# exam.net
KiCad netlist of a schematic drawn in Altium Designer
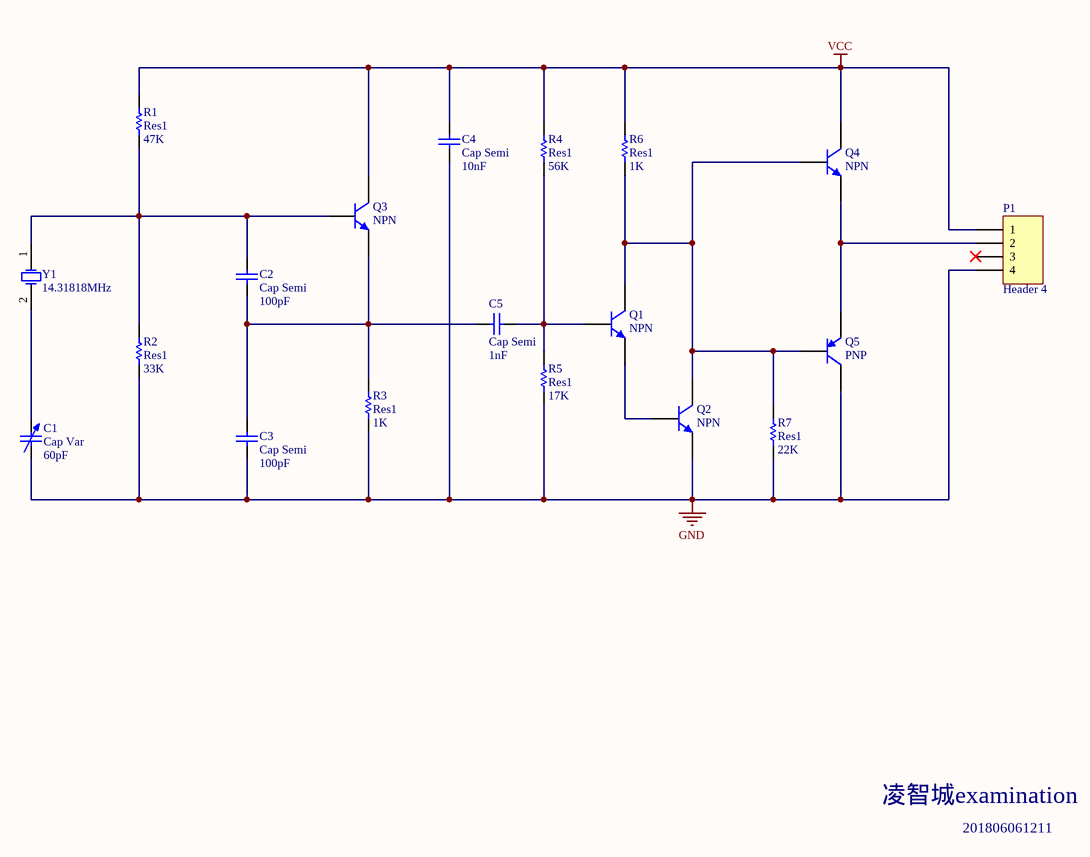
[diagram p0: exam.SchDoc]

(export (version "E")
  (design (tool "Eeschema 10.0.6"))
  (components
    (comp (ref "C1")
      (value "Cap Var")
      (footprint "C1210_N")
      (description "Variable or Adjustable Capacitor")
      (fields (field (name "ALTIUM_VALUE") "60pF") (field (name "PUBLISHER") "Altium Limited"))
      (libsource (lib "exam") (part "Cap Var"))
    )
    (comp (ref "C2")
      (value "Cap Semi")
      (footprint "C1206")
      (description "Capacitor (Semiconductor SIM Model)")
      (fields (field (name "ALTIUM_VALUE") "100pF") (field (name "PUBLISHER") "Altium Limited"))
      (libsource (lib "exam") (part "Cap Semi"))
    )
    (comp (ref "C3")
      (value "Cap Semi")
      (footprint "C1206")
      (description "Capacitor (Semiconductor SIM Model)")
      (fields (field (name "ALTIUM_VALUE") "100pF") (field (name "PUBLISHER") "Altium Limited"))
      (libsource (lib "exam") (part "Cap Semi"))
    )
    (comp (ref "C4")
      (value "Cap Semi")
      (footprint "C1206")
      (description "Capacitor (Semiconductor SIM Model)")
      (fields (field (name "ALTIUM_VALUE") "10nF") (field (name "PUBLISHER") "Altium Limited"))
      (libsource (lib "exam") (part "Cap Semi"))
    )
    (comp (ref "C5")
      (value "Cap Semi")
      (footprint "C1206")
      (description "Capacitor (Semiconductor SIM Model)")
      (fields (field (name "ALTIUM_VALUE") "1nF") (field (name "PUBLISHER") "Altium Limited"))
      (libsource (lib "exam") (part "Cap Semi"))
    )
    (comp (ref "P1")
      (value "Header 4")
      (footprint "HDR1X4")
      (description "Header, 4-Pin")
      (fields (field (name "PUBLISHER") "Altium Limited"))
      (libsource (lib "exam") (part "Header 4"))
    )
    (comp (ref "Q1")
      (value "NPN")
      (footprint "TO-226-AA")
      (description "NPN Bipolar Transistor")
      (fields (field (name "PUBLISHER") "Altium Limited"))
      (libsource (lib "exam") (part "NPN"))
    )
    (comp (ref "Q2")
      (value "NPN")
      (footprint "TO-226-AA")
      (description "NPN Bipolar Transistor")
      (fields (field (name "PUBLISHER") "Altium Limited"))
      (libsource (lib "exam") (part "NPN"))
    )
    (comp (ref "Q3")
      (value "NPN")
      (footprint "TO-226-AA")
      (description "NPN Bipolar Transistor")
      (fields (field (name "PUBLISHER") "Altium Limited"))
      (libsource (lib "exam") (part "NPN"))
    )
    (comp (ref "Q4")
      (value "NPN")
      (footprint "TO-226-AA")
      (description "NPN Bipolar Transistor")
      (fields (field (name "PUBLISHER") "Altium Limited"))
      (libsource (lib "exam") (part "NPN"))
    )
    (comp (ref "Q5")
      (value "PNP")
      (footprint "SOT-23B_N")
      (description "PNP Bipolar Transistor")
      (fields (field (name "PUBLISHER") "Altium Limited"))
      (libsource (lib "exam") (part "PNP"))
    )
    (comp (ref "R1")
      (value "Res1")
      (footprint "AXIAL-0.3")
      (description "Resistor")
      (fields (field (name "ALTIUM_VALUE") "47K") (field (name "PUBLISHER") "Altium Limited"))
      (libsource (lib "exam") (part "Res1"))
    )
    (comp (ref "R2")
      (value "Res1")
      (footprint "AXIAL-0.3")
      (description "Resistor")
      (fields (field (name "ALTIUM_VALUE") "33K") (field (name "PUBLISHER") "Altium Limited"))
      (libsource (lib "exam") (part "Res1"))
    )
    (comp (ref "R3")
      (value "Res1")
      (footprint "AXIAL-0.3")
      (description "Resistor")
      (fields (field (name "ALTIUM_VALUE") "1K") (field (name "PUBLISHER") "Altium Limited"))
      (libsource (lib "exam") (part "Res1"))
    )
    (comp (ref "R4")
      (value "Res1")
      (footprint "AXIAL-0.3")
      (description "Resistor")
      (fields (field (name "ALTIUM_VALUE") "56K") (field (name "PUBLISHER") "Altium Limited"))
      (libsource (lib "exam") (part "Res1"))
    )
    (comp (ref "R5")
      (value "Res1")
      (footprint "AXIAL-0.3")
      (description "Resistor")
      (fields (field (name "ALTIUM_VALUE") "17K") (field (name "PUBLISHER") "Altium Limited"))
      (libsource (lib "exam") (part "Res1"))
    )
    (comp (ref "R6")
      (value "Res1")
      (footprint "AXIAL-0.3")
      (description "Resistor")
      (fields (field (name "ALTIUM_VALUE") "1K") (field (name "PUBLISHER") "Altium Limited"))
      (libsource (lib "exam") (part "Res1"))
    )
    (comp (ref "R7")
      (value "Res1")
      (footprint "AXIAL-0.3")
      (description "Resistor")
      (fields (field (name "ALTIUM_VALUE") "22K") (field (name "PUBLISHER") "Altium Limited"))
      (libsource (lib "exam") (part "Res1"))
    )
    (comp (ref "Y1")
      (value "14.31818MHz")
      (footprint "R38")
      (description "Crystal Oscillator")
      (fields (field (name "PUBLISHER") "Altium Limited"))
      (libsource (lib "exam") (part "XTAL"))
    )
  )
  (nets
    (net (code "1") (name "GND") (class "Default")
      (node (ref "C1") (pin "1") (pinfunction "1_1") (pintype "passive"))
      (node (ref "C3") (pin "1") (pinfunction "1_1") (pintype "passive"))
      (node (ref "C4") (pin "1") (pinfunction "1_1") (pintype "passive"))
      (node (ref "P1") (pin "4") (pinfunction "4_4") (pintype "passive"))
      (node (ref "Q2") (pin "3") (pinfunction "E_3") (pintype "passive"))
      (node (ref "Q5") (pin "1") (pinfunction "C_1") (pintype "passive"))
      (node (ref "R2") (pin "1") (pinfunction "1_1") (pintype "passive"))
      (node (ref "R3") (pin "1") (pinfunction "1_1") (pintype "passive"))
      (node (ref "R5") (pin "1") (pinfunction "1_1") (pintype "passive"))
      (node (ref "R7") (pin "1") (pinfunction "1_1") (pintype "passive"))
    )
    (net (code "2") (name "Net-(Q1-B)") (class "Default")
      (node (ref "C5") (pin "2") (pinfunction "2_2") (pintype "passive"))
      (node (ref "Q1") (pin "2") (pinfunction "B_2") (pintype "passive"))
      (node (ref "R4") (pin "1") (pinfunction "1_1") (pintype "passive"))
      (node (ref "R5") (pin "2") (pinfunction "2_2") (pintype "passive"))
    )
    (net (code "3") (name "Net-(Q1-C)") (class "Default")
      (node (ref "Q1") (pin "1") (pinfunction "C_1") (pintype "passive"))
      (node (ref "Q2") (pin "1") (pinfunction "C_1") (pintype "passive"))
      (node (ref "Q4") (pin "2") (pinfunction "B_2") (pintype "passive"))
      (node (ref "Q5") (pin "2") (pinfunction "B_2") (pintype "passive"))
      (node (ref "R6") (pin "1") (pinfunction "1_1") (pintype "passive"))
      (node (ref "R7") (pin "2") (pinfunction "2_2") (pintype "passive"))
    )
    (net (code "4") (name "Net-(Q1-E)") (class "Default")
      (node (ref "Q1") (pin "3") (pinfunction "E_3") (pintype "passive"))
      (node (ref "Q2") (pin "2") (pinfunction "B_2") (pintype "passive"))
    )
    (net (code "5") (name "Net-(Q3-B)") (class "Default")
      (node (ref "C2") (pin "2") (pinfunction "2_2") (pintype "passive"))
      (node (ref "Q3") (pin "2") (pinfunction "B_2") (pintype "passive"))
      (node (ref "R1") (pin "1") (pinfunction "1_1") (pintype "passive"))
      (node (ref "R2") (pin "2") (pinfunction "2_2") (pintype "passive"))
      (node (ref "Y1") (pin "1") (pinfunction "OSC1_1") (pintype "passive"))
    )
    (net (code "6") (name "Net-(Q3-E)") (class "Default")
      (node (ref "C2") (pin "1") (pinfunction "1_1") (pintype "passive"))
      (node (ref "C3") (pin "2") (pinfunction "2_2") (pintype "passive"))
      (node (ref "C5") (pin "1") (pinfunction "1_1") (pintype "passive"))
      (node (ref "Q3") (pin "3") (pinfunction "E_3") (pintype "passive"))
      (node (ref "R3") (pin "2") (pinfunction "2_2") (pintype "passive"))
    )
    (net (code "7") (name "Net-(Q4-E)") (class "Default")
      (node (ref "P1") (pin "2") (pinfunction "2_2") (pintype "passive"))
      (node (ref "Q4") (pin "3") (pinfunction "E_3") (pintype "passive"))
      (node (ref "Q5") (pin "3") (pinfunction "E_3") (pintype "passive"))
    )
    (net (code "8") (name "Net-(Y1-OSC2)") (class "Default")
      (node (ref "C1") (pin "2") (pinfunction "2_2") (pintype "passive"))
      (node (ref "Y1") (pin "2") (pinfunction "OSC2_2") (pintype "passive"))
    )
    (net (code "9") (name "VCC") (class "Default")
      (node (ref "C4") (pin "2") (pinfunction "2_2") (pintype "passive"))
      (node (ref "P1") (pin "1") (pinfunction "1_1") (pintype "passive"))
      (node (ref "Q3") (pin "1") (pinfunction "C_1") (pintype "passive"))
      (node (ref "Q4") (pin "1") (pinfunction "C_1") (pintype "passive"))
      (node (ref "R1") (pin "2") (pinfunction "2_2") (pintype "passive"))
      (node (ref "R4") (pin "2") (pinfunction "2_2") (pintype "passive"))
      (node (ref "R6") (pin "2") (pinfunction "2_2") (pintype "passive"))
    )
    (net (code "10") (name "unconnected-(P1-Pad3)") (class "Default")
      (node (ref "P1") (pin "3") (pinfunction "3_3") (pintype "passive+no_connect"))
    )
  )
)
